# Output.net
KiCad netlist of a schematic drawn in EAGLE
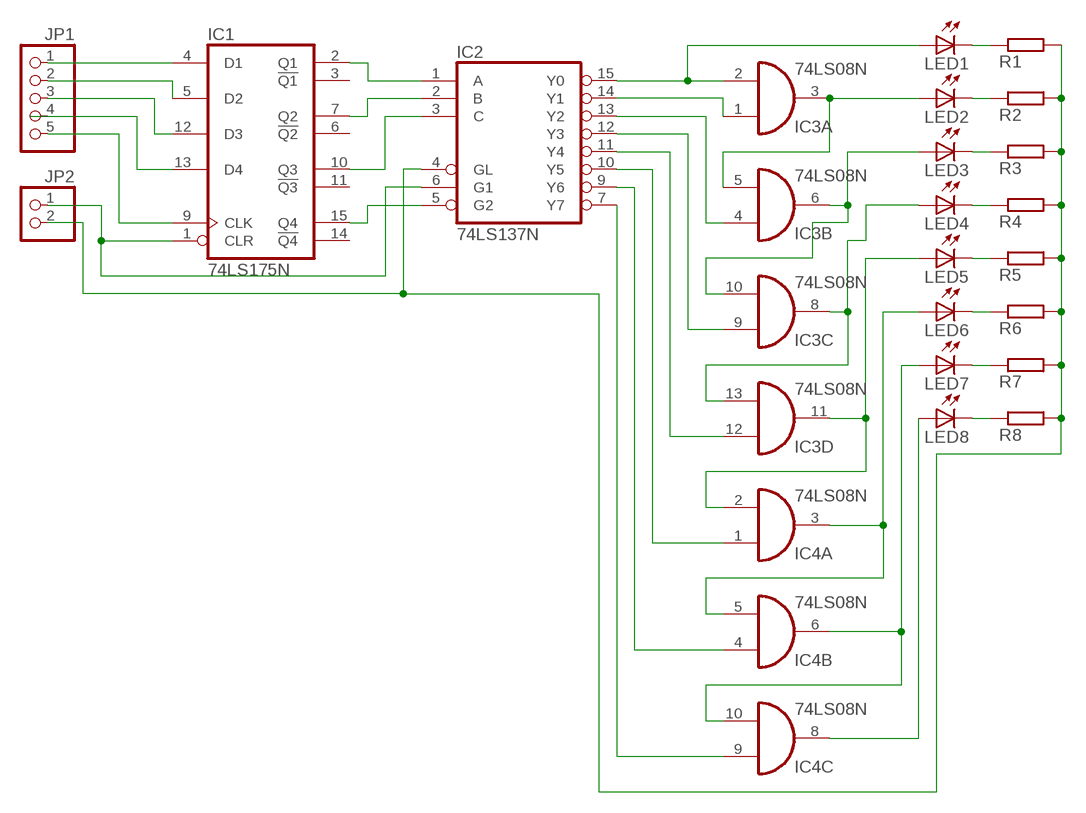
[diagram p0: schematic, sheet 1]

(export (version "E")
  (design (tool "Eeschema 10.0.6"))
  (components
    (comp (ref "IC1")
      (value "74LS175N")
      (footprint "eagle-import:DIL16")
      (libsource (lib "eagle-import") (part "74175NLS"))
    )
    (comp (ref "IC2")
      (value "74LS137N")
      (footprint "eagle-import:DIL16")
      (libsource (lib "eagle-import") (part "74137NLS"))
    )
    (comp (ref "IC3")
      (value "74LS08N")
      (footprint "eagle-import:DIL14")
      (libsource (lib "eagle-import") (part "7408NLS"))
    )
    (comp (ref "IC4")
      (value "74LS08N")
      (footprint "eagle-import:DIL14")
      (libsource (lib "eagle-import") (part "7408NLS"))
    )
    (comp (ref "JP1")
      (value "PINHD-1X5")
      (footprint "eagle-import:1X05")
      (libsource (lib "eagle-import") (part "PINHD-1X5"))
    )
    (comp (ref "JP2")
      (value "PINHD-1X2")
      (footprint "eagle-import:1X02")
      (libsource (lib "eagle-import") (part "PINHD-1X2"))
    )
    (comp (ref "LED1")
      (value "LED5MM")
      (footprint "eagle-import:LED5MM")
      (libsource (lib "eagle-import") (part "LED5MM"))
    )
    (comp (ref "LED2")
      (value "LED5MM")
      (footprint "eagle-import:LED5MM")
      (libsource (lib "eagle-import") (part "LED5MM"))
    )
    (comp (ref "LED3")
      (value "LED5MM")
      (footprint "eagle-import:LED5MM")
      (libsource (lib "eagle-import") (part "LED5MM"))
    )
    (comp (ref "LED4")
      (value "LED5MM")
      (footprint "eagle-import:LED5MM")
      (libsource (lib "eagle-import") (part "LED5MM"))
    )
    (comp (ref "LED5")
      (value "LED5MM")
      (footprint "eagle-import:LED5MM")
      (libsource (lib "eagle-import") (part "LED5MM"))
    )
    (comp (ref "LED6")
      (value "LED5MM")
      (footprint "eagle-import:LED5MM")
      (libsource (lib "eagle-import") (part "LED5MM"))
    )
    (comp (ref "LED7")
      (value "LED5MM")
      (footprint "eagle-import:LED5MM")
      (libsource (lib "eagle-import") (part "LED5MM"))
    )
    (comp (ref "LED8")
      (value "LED5MM")
      (footprint "eagle-import:LED5MM")
      (libsource (lib "eagle-import") (part "LED5MM"))
    )
    (comp (ref "R1")
      (value "R-EU_0207/10")
      (footprint "eagle-import:0207_10")
      (libsource (lib "eagle-import") (part "R-EU_0207/10"))
    )
    (comp (ref "R2")
      (value "R-EU_0207/10")
      (footprint "eagle-import:0207_10")
      (libsource (lib "eagle-import") (part "R-EU_0207/10"))
    )
    (comp (ref "R3")
      (value "R-EU_0207/10")
      (footprint "eagle-import:0207_10")
      (libsource (lib "eagle-import") (part "R-EU_0207/10"))
    )
    (comp (ref "R4")
      (value "R-EU_0207/10")
      (footprint "eagle-import:0207_10")
      (libsource (lib "eagle-import") (part "R-EU_0207/10"))
    )
    (comp (ref "R5")
      (value "R-EU_0207/10")
      (footprint "eagle-import:0207_10")
      (libsource (lib "eagle-import") (part "R-EU_0207/10"))
    )
    (comp (ref "R6")
      (value "R-EU_0207/10")
      (footprint "eagle-import:0207_10")
      (libsource (lib "eagle-import") (part "R-EU_0207/10"))
    )
    (comp (ref "R7")
      (value "R-EU_0207/10")
      (footprint "eagle-import:0207_10")
      (libsource (lib "eagle-import") (part "R-EU_0207/10"))
    )
    (comp (ref "R8")
      (value "R-EU_0207/10")
      (footprint "eagle-import:0207_10")
      (libsource (lib "eagle-import") (part "R-EU_0207/10"))
    )
  )
  (nets
    (net (code "1") (name "Net-(IC1A-CLK)") (class "Default")
      (node (ref "IC1") (pin "9") (pinfunction "CLK_9") (pintype "input"))
      (node (ref "JP1") (pin "5") (pinfunction "5_5") (pintype "passive"))
    )
    (net (code "2") (name "Net-(IC1A-CLR)") (class "Default")
      (node (ref "IC1") (pin "1") (pinfunction "CLR_1") (pintype "input"))
      (node (ref "IC2") (pin "6") (pinfunction "G1_6") (pintype "input"))
      (node (ref "JP2") (pin "1") (pinfunction "1_1") (pintype "passive"))
    )
    (net (code "3") (name "Net-(IC1A-D1)") (class "Default")
      (node (ref "IC1") (pin "4") (pinfunction "D1_4") (pintype "input"))
      (node (ref "JP1") (pin "1") (pinfunction "1_1") (pintype "passive"))
    )
    (net (code "4") (name "Net-(IC1A-D2)") (class "Default")
      (node (ref "IC1") (pin "5") (pinfunction "D2_5") (pintype "input"))
      (node (ref "JP1") (pin "2") (pinfunction "2_2") (pintype "passive"))
    )
    (net (code "5") (name "Net-(IC1A-D3)") (class "Default")
      (node (ref "IC1") (pin "12") (pinfunction "D3_12") (pintype "input"))
      (node (ref "JP1") (pin "3") (pinfunction "3_3") (pintype "passive"))
    )
    (net (code "6") (name "Net-(IC1A-Q1)") (class "Default")
      (node (ref "IC1") (pin "2") (pinfunction "Q1_2") (pintype "output"))
      (node (ref "IC2") (pin "1") (pinfunction "A_1") (pintype "input"))
    )
    (net (code "7") (name "Net-(IC1A-Q2)") (class "Default")
      (node (ref "IC1") (pin "7") (pinfunction "Q2_7") (pintype "output"))
      (node (ref "IC2") (pin "2") (pinfunction "B_2") (pintype "input"))
    )
    (net (code "8") (name "Net-(IC1A-Q3)") (class "Default")
      (node (ref "IC1") (pin "10") (pinfunction "Q3_10") (pintype "output"))
      (node (ref "IC2") (pin "3") (pinfunction "C_3") (pintype "input"))
    )
    (net (code "9") (name "Net-(IC1A-Q4)") (class "Default")
      (node (ref "IC1") (pin "15") (pinfunction "Q4_15") (pintype "output"))
      (node (ref "IC2") (pin "5") (pinfunction "G2_5") (pintype "input"))
    )
    (net (code "10") (name "Net-(IC2A-GL)") (class "Default")
      (node (ref "IC2") (pin "4") (pinfunction "GL_4") (pintype "input"))
      (node (ref "JP2") (pin "2") (pinfunction "2_2") (pintype "passive"))
      (node (ref "R1") (pin "2") (pinfunction "2_2") (pintype "passive"))
      (node (ref "R2") (pin "2") (pinfunction "2_2") (pintype "passive"))
      (node (ref "R3") (pin "2") (pinfunction "2_2") (pintype "passive"))
      (node (ref "R4") (pin "2") (pinfunction "2_2") (pintype "passive"))
      (node (ref "R5") (pin "2") (pinfunction "2_2") (pintype "passive"))
      (node (ref "R6") (pin "2") (pinfunction "2_2") (pintype "passive"))
      (node (ref "R7") (pin "2") (pinfunction "2_2") (pintype "passive"))
      (node (ref "R8") (pin "2") (pinfunction "2_2") (pintype "passive"))
    )
    (net (code "11") (name "Net-(IC2A-Y0)") (class "Default")
      (node (ref "IC2") (pin "15") (pinfunction "Y0_15") (pintype "output"))
      (node (ref "IC3") (pin "2") (pinfunction "I1_2") (pintype "input"))
      (node (ref "LED1") (pin "A") (pinfunction "A_A") (pintype "passive"))
    )
    (net (code "12") (name "Net-(IC2A-Y1)") (class "Default")
      (node (ref "IC2") (pin "14") (pinfunction "Y1_14") (pintype "output"))
      (node (ref "IC3") (pin "1") (pinfunction "I0_1") (pintype "input"))
    )
    (net (code "13") (name "Net-(IC2A-Y2)") (class "Default")
      (node (ref "IC2") (pin "13") (pinfunction "Y2_13") (pintype "output"))
      (node (ref "IC3") (pin "4") (pinfunction "I0_4") (pintype "input"))
    )
    (net (code "14") (name "Net-(IC2A-Y3)") (class "Default")
      (node (ref "IC2") (pin "12") (pinfunction "Y3_12") (pintype "output"))
      (node (ref "IC3") (pin "9") (pinfunction "I0_9") (pintype "input"))
    )
    (net (code "15") (name "Net-(IC2A-Y4)") (class "Default")
      (node (ref "IC2") (pin "11") (pinfunction "Y4_11") (pintype "output"))
      (node (ref "IC3") (pin "12") (pinfunction "I0_12") (pintype "input"))
    )
    (net (code "16") (name "Net-(IC2A-Y5)") (class "Default")
      (node (ref "IC2") (pin "10") (pinfunction "Y5_10") (pintype "output"))
      (node (ref "IC4") (pin "1") (pinfunction "I0_1") (pintype "input"))
    )
    (net (code "17") (name "Net-(IC2A-Y6)") (class "Default")
      (node (ref "IC2") (pin "9") (pinfunction "Y6_9") (pintype "output"))
      (node (ref "IC4") (pin "4") (pinfunction "I0_4") (pintype "input"))
    )
    (net (code "18") (name "Net-(IC2A-Y7)") (class "Default")
      (node (ref "IC2") (pin "7") (pinfunction "Y7_7") (pintype "output"))
      (node (ref "IC4") (pin "9") (pinfunction "I0_9") (pintype "input"))
    )
    (net (code "19") (name "Net-(IC3A-O)") (class "Default")
      (node (ref "IC3") (pin "3") (pinfunction "O_3") (pintype "output"))
      (node (ref "IC3") (pin "5") (pinfunction "I1_5") (pintype "input"))
      (node (ref "LED2") (pin "A") (pinfunction "A_A") (pintype "passive"))
    )
    (net (code "20") (name "Net-(IC3B-O)") (class "Default")
      (node (ref "IC3") (pin "10") (pinfunction "I1_10") (pintype "input"))
      (node (ref "IC3") (pin "6") (pinfunction "O_6") (pintype "output"))
      (node (ref "LED3") (pin "A") (pinfunction "A_A") (pintype "passive"))
    )
    (net (code "21") (name "Net-(IC3C-O)") (class "Default")
      (node (ref "IC3") (pin "13") (pinfunction "I1_13") (pintype "input"))
      (node (ref "IC3") (pin "8") (pinfunction "O_8") (pintype "output"))
      (node (ref "LED4") (pin "A") (pinfunction "A_A") (pintype "passive"))
    )
    (net (code "22") (name "Net-(IC3D-O)") (class "Default")
      (node (ref "IC3") (pin "11") (pinfunction "O_11") (pintype "output"))
      (node (ref "IC4") (pin "2") (pinfunction "I1_2") (pintype "input"))
      (node (ref "LED5") (pin "A") (pinfunction "A_A") (pintype "passive"))
    )
    (net (code "23") (name "Net-(IC4A-O)") (class "Default")
      (node (ref "IC4") (pin "3") (pinfunction "O_3") (pintype "output"))
      (node (ref "IC4") (pin "5") (pinfunction "I1_5") (pintype "input"))
      (node (ref "LED6") (pin "A") (pinfunction "A_A") (pintype "passive"))
    )
    (net (code "24") (name "Net-(IC4B-O)") (class "Default")
      (node (ref "IC4") (pin "10") (pinfunction "I1_10") (pintype "input"))
      (node (ref "IC4") (pin "6") (pinfunction "O_6") (pintype "output"))
      (node (ref "LED7") (pin "A") (pinfunction "A_A") (pintype "passive"))
    )
    (net (code "25") (name "Net-(IC4C-O)") (class "Default")
      (node (ref "IC4") (pin "8") (pinfunction "O_8") (pintype "output"))
      (node (ref "LED8") (pin "A") (pinfunction "A_A") (pintype "passive"))
    )
    (net (code "26") (name "Net-(LED1-C)") (class "Default")
      (node (ref "LED1") (pin "K") (pinfunction "C_K") (pintype "passive"))
      (node (ref "R1") (pin "1") (pinfunction "1_1") (pintype "passive"))
    )
    (net (code "27") (name "Net-(LED2-C)") (class "Default")
      (node (ref "LED2") (pin "K") (pinfunction "C_K") (pintype "passive"))
      (node (ref "R2") (pin "1") (pinfunction "1_1") (pintype "passive"))
    )
    (net (code "28") (name "Net-(LED3-C)") (class "Default")
      (node (ref "LED3") (pin "K") (pinfunction "C_K") (pintype "passive"))
      (node (ref "R3") (pin "1") (pinfunction "1_1") (pintype "passive"))
    )
    (net (code "29") (name "Net-(LED4-C)") (class "Default")
      (node (ref "LED4") (pin "K") (pinfunction "C_K") (pintype "passive"))
      (node (ref "R4") (pin "1") (pinfunction "1_1") (pintype "passive"))
    )
    (net (code "30") (name "Net-(LED5-C)") (class "Default")
      (node (ref "LED5") (pin "K") (pinfunction "C_K") (pintype "passive"))
      (node (ref "R5") (pin "1") (pinfunction "1_1") (pintype "passive"))
    )
    (net (code "31") (name "Net-(LED6-C)") (class "Default")
      (node (ref "LED6") (pin "K") (pinfunction "C_K") (pintype "passive"))
      (node (ref "R6") (pin "1") (pinfunction "1_1") (pintype "passive"))
    )
    (net (code "32") (name "Net-(LED7-C)") (class "Default")
      (node (ref "LED7") (pin "K") (pinfunction "C_K") (pintype "passive"))
      (node (ref "R7") (pin "1") (pinfunction "1_1") (pintype "passive"))
    )
    (net (code "33") (name "Net-(LED8-C)") (class "Default")
      (node (ref "LED8") (pin "K") (pinfunction "C_K") (pintype "passive"))
      (node (ref "R8") (pin "1") (pinfunction "1_1") (pintype "passive"))
    )
    (net (code "34") (name "unconnected-(IC1A-D4-Pad13)") (class "Default")
      (node (ref "IC1") (pin "13") (pinfunction "D4_13") (pintype "input"))
    )
    (net (code "35") (name "unconnected-(IC1A-~{Q1}-Pad3)") (class "Default")
      (node (ref "IC1") (pin "3") (pinfunction "~{Q1}_3") (pintype "output"))
    )
    (net (code "36") (name "unconnected-(IC1A-~{Q2}-Pad6)") (class "Default")
      (node (ref "IC1") (pin "6") (pinfunction "~{Q2}_6") (pintype "output"))
    )
    (net (code "37") (name "unconnected-(IC1A-~{Q3}-Pad11)") (class "Default")
      (node (ref "IC1") (pin "11") (pinfunction "~{Q3}_11") (pintype "output"))
    )
    (net (code "38") (name "unconnected-(IC1A-~{Q4}-Pad14)") (class "Default")
      (node (ref "IC1") (pin "14") (pinfunction "~{Q4}_14") (pintype "output"))
    )
    (net (code "39") (name "unconnected-(JP1-Pad4)") (class "Default")
      (node (ref "JP1") (pin "4") (pinfunction "4_4") (pintype "passive"))
    )
  )
)
